# Sensors.net
KiCad netlist of a schematic drawn in Altium Designer
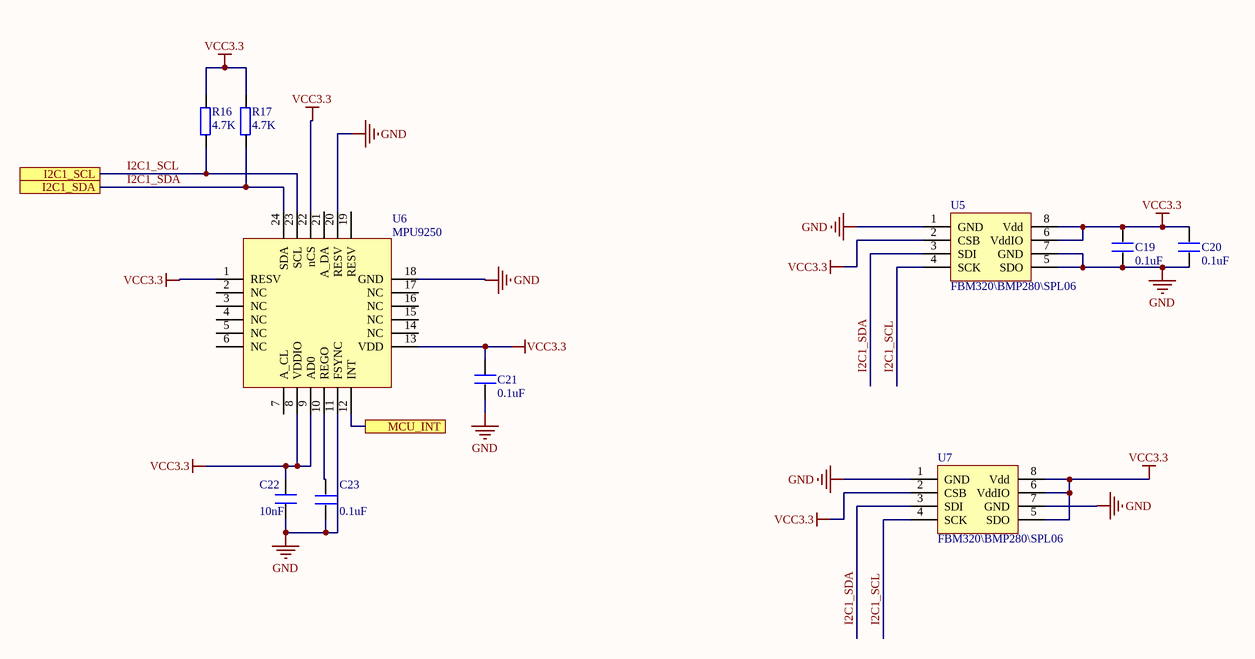
[diagram p0: Sensors.SchDoc]

(export (version "E")
  (design (tool "Eeschema 10.0.6"))
  (components
    (comp (ref "C19")
      (value "0.1uF")
      (footprint "0603P")
      (libsource (lib "Explorer STM32F407封装库") (part "C"))
    )
    (comp (ref "C20")
      (value "0.1uF")
      (footprint "0603P")
      (libsource (lib "Explorer STM32F407封装库") (part "C"))
    )
    (comp (ref "C21")
      (value "0.1uF")
      (footprint "0603P")
      (libsource (lib "Explorer STM32F407封装库") (part "C"))
    )
    (comp (ref "C22") (value "10nF") (footprint "0603P") (libsource (lib "Explorer STM32F407封装库") (part "C")))
    (comp (ref "C23")
      (value "0.1uF")
      (footprint "0603P")
      (libsource (lib "Explorer STM32F407封装库") (part "C"))
    )
    (comp (ref "R16") (value "4.7K") (footprint "0603P") (libsource (lib "Explorer STM32F407封装库") (part "R")))
    (comp (ref "R17") (value "4.7K") (footprint "0603P") (libsource (lib "Explorer STM32F407封装库") (part "R")))
    (comp (ref "U5")
      (value "FBM32~{0}BMP28~{0}SPL06")
      (footprint "LGA-2_5X2MM")
      (description "气压计")
      (fields (field (name "PUBLISHER") "mazhongwei"))
      (libsource (lib "RoboFly") (part "FBM320"))
    )
    (comp (ref "U6")
      (value "MPU9250")
      (footprint "MiniFly :QFN24-0.4")
      (libsource (lib "RoboFly") (part "MPU9250"))
    )
    (comp (ref "U7")
      (value "FBM32~{0}BMP28~{0}SPL06")
      (footprint "LGA-2_5X2MM")
      (description "气压计")
      (fields (field (name "PUBLISHER") "mazhongwei"))
      (libsource (lib "RoboFly") (part "FBM320"))
    )
  )
  (nets
    (net (code "1") (name "/I2C1_SCL") (class "Default")
      (node (ref "R16") (pin "2") (pintype "passive"))
      (node (ref "U5") (pin "4") (pinfunction "SCK_4") (pintype "passive"))
      (node (ref "U6") (pin "23") (pinfunction "SCL_23") (pintype "passive"))
      (node (ref "U7") (pin "4") (pinfunction "SCK_4") (pintype "passive"))
    )
    (net (code "2") (name "/I2C1_SDA") (class "Default")
      (node (ref "R17") (pin "2") (pintype "passive"))
      (node (ref "U5") (pin "3") (pinfunction "SDI_3") (pintype "passive"))
      (node (ref "U6") (pin "24") (pinfunction "SDA_24") (pintype "passive"))
      (node (ref "U7") (pin "3") (pinfunction "SDI_3") (pintype "passive"))
    )
    (net (code "3") (name "/MCU_INT") (class "Default")
      (node (ref "U6") (pin "12") (pinfunction "INT_12") (pintype "passive"))
    )
    (net (code "4") (name "GND") (class "Default")
      (node (ref "C19") (pin "1") (pintype "passive"))
      (node (ref "C20") (pin "1") (pintype "passive"))
      (node (ref "C21") (pin "1") (pintype "passive"))
      (node (ref "C22") (pin "1") (pintype "passive"))
      (node (ref "C23") (pin "2") (pintype "passive"))
      (node (ref "U5") (pin "1") (pinfunction "GND_1") (pintype "passive"))
      (node (ref "U5") (pin "5") (pinfunction "SDO_5") (pintype "passive"))
      (node (ref "U5") (pin "7") (pinfunction "GND_7") (pintype "passive"))
      (node (ref "U6") (pin "11") (pinfunction "FSYNC_11") (pintype "passive"))
      (node (ref "U6") (pin "18") (pinfunction "GND_18") (pintype "passive"))
      (node (ref "U6") (pin "20") (pinfunction "RESV_20") (pintype "passive"))
      (node (ref "U7") (pin "1") (pinfunction "GND_1") (pintype "passive"))
      (node (ref "U7") (pin "7") (pinfunction "GND_7") (pintype "passive"))
    )
    (net (code "5") (name "Net-(U6-REGO)") (class "Default")
      (node (ref "C23") (pin "1") (pintype "passive"))
      (node (ref "U6") (pin "10") (pinfunction "REGO_10") (pintype "passive"))
    )
    (net (code "6") (name "VCC3.3") (class "Default")
      (node (ref "C19") (pin "2") (pintype "passive"))
      (node (ref "C20") (pin "2") (pintype "passive"))
      (node (ref "C21") (pin "2") (pintype "passive"))
      (node (ref "C22") (pin "2") (pintype "passive"))
      (node (ref "R16") (pin "1") (pintype "passive"))
      (node (ref "R17") (pin "1") (pintype "passive"))
      (node (ref "U5") (pin "2") (pinfunction "CSB_2") (pintype "passive"))
      (node (ref "U5") (pin "6") (pinfunction "VddIO_6") (pintype "passive"))
      (node (ref "U5") (pin "8") (pinfunction "Vdd_8") (pintype "passive"))
      (node (ref "U6") (pin "1") (pinfunction "RESV_1") (pintype "passive"))
      (node (ref "U6") (pin "13") (pinfunction "VDD_13") (pintype "passive"))
      (node (ref "U6") (pin "22") (pinfunction "nCS_22") (pintype "passive"))
      (node (ref "U6") (pin "8") (pinfunction "VDDIO_8") (pintype "passive"))
      (node (ref "U6") (pin "9") (pinfunction "AD0_9") (pintype "passive"))
      (node (ref "U7") (pin "2") (pinfunction "CSB_2") (pintype "passive"))
      (node (ref "U7") (pin "5") (pinfunction "SDO_5") (pintype "passive"))
      (node (ref "U7") (pin "6") (pinfunction "VddIO_6") (pintype "passive"))
      (node (ref "U7") (pin "8") (pinfunction "Vdd_8") (pintype "passive"))
    )
    (net (code "7") (name "unconnected-(U6-A_CL-Pad7)") (class "Default")
      (node (ref "U6") (pin "7") (pinfunction "A_CL_7") (pintype "passive"))
    )
    (net (code "8") (name "unconnected-(U6-A_DA-Pad21)") (class "Default")
      (node (ref "U6") (pin "21") (pinfunction "A_DA_21") (pintype "passive"))
    )
    (net (code "9") (name "unconnected-(U6-NC-Pad2)") (class "Default")
      (node (ref "U6") (pin "2") (pinfunction "NC_2") (pintype "passive"))
    )
    (net (code "10") (name "unconnected-(U6-NC-Pad3)") (class "Default")
      (node (ref "U6") (pin "3") (pinfunction "NC_3") (pintype "passive"))
    )
    (net (code "11") (name "unconnected-(U6-NC-Pad4)") (class "Default")
      (node (ref "U6") (pin "4") (pinfunction "NC_4") (pintype "passive"))
    )
    (net (code "12") (name "unconnected-(U6-NC-Pad5)") (class "Default")
      (node (ref "U6") (pin "5") (pinfunction "NC_5") (pintype "passive"))
    )
    (net (code "13") (name "unconnected-(U6-NC-Pad6)") (class "Default")
      (node (ref "U6") (pin "6") (pinfunction "NC_6") (pintype "passive"))
    )
    (net (code "14") (name "unconnected-(U6-NC-Pad14)") (class "Default")
      (node (ref "U6") (pin "14") (pinfunction "NC_14") (pintype "passive"))
    )
    (net (code "15") (name "unconnected-(U6-NC-Pad15)") (class "Default")
      (node (ref "U6") (pin "15") (pinfunction "NC_15") (pintype "passive"))
    )
    (net (code "16") (name "unconnected-(U6-NC-Pad16)") (class "Default")
      (node (ref "U6") (pin "16") (pinfunction "NC_16") (pintype "passive"))
    )
    (net (code "17") (name "unconnected-(U6-NC-Pad17)") (class "Default")
      (node (ref "U6") (pin "17") (pinfunction "NC_17") (pintype "passive"))
    )
    (net (code "18") (name "unconnected-(U6-RESV-Pad19)") (class "Default")
      (node (ref "U6") (pin "19") (pinfunction "RESV_19") (pintype "passive"))
    )
  )
)
